# Xmega.net
KiCad netlist of a schematic drawn in EAGLE
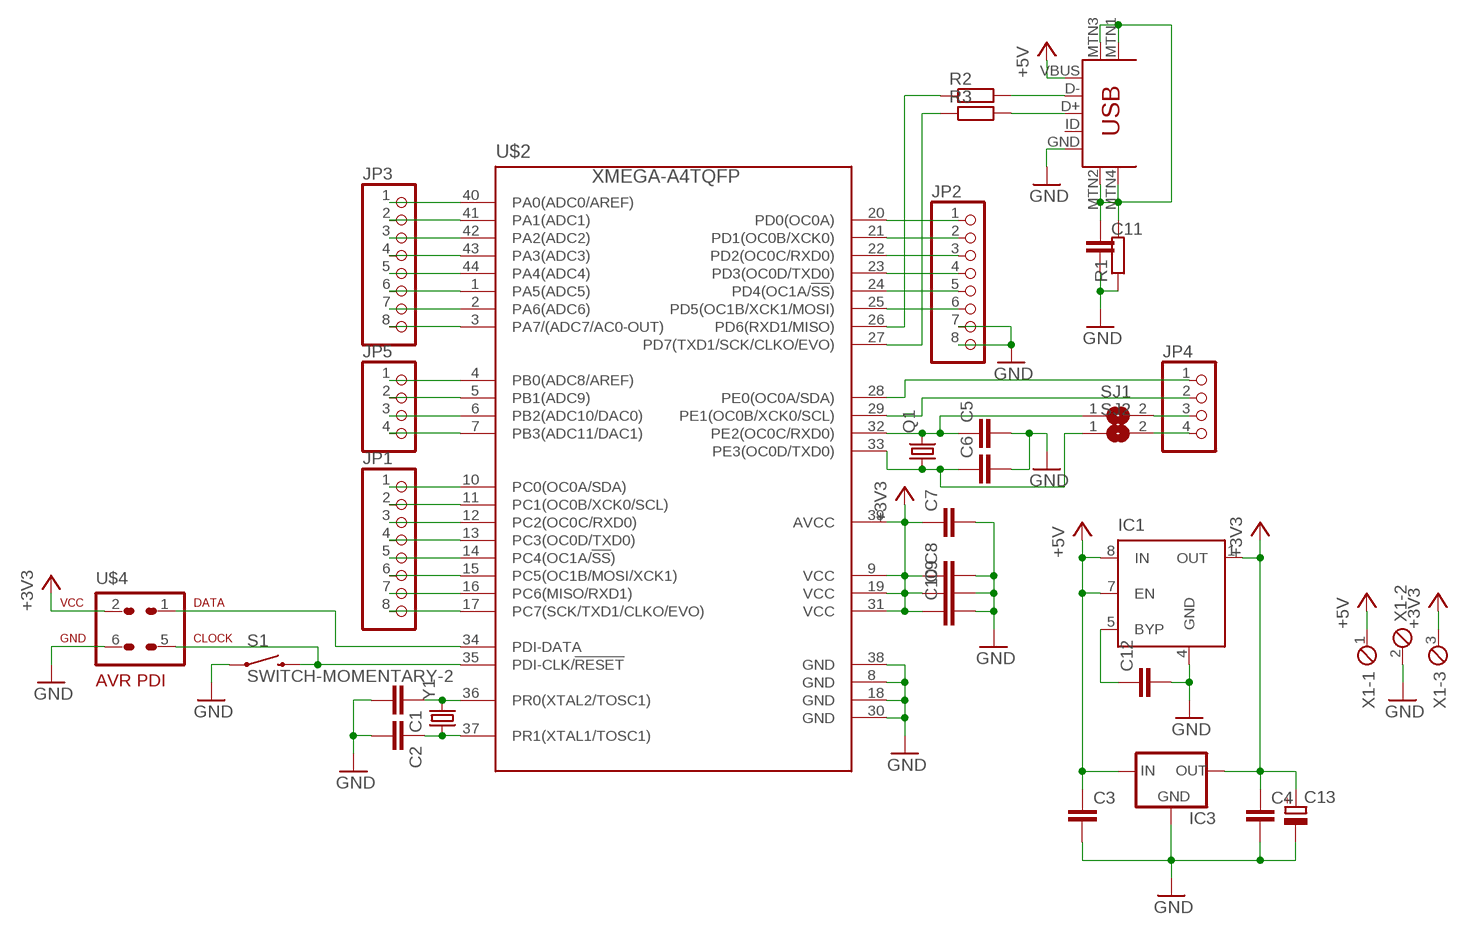
[diagram p0: schematic, sheet 1]

(export (version "E")
  (design (tool "Eeschema 10.0.6"))
  (components
    (comp (ref "C1")
      (value "C-EUC0603")
      (footprint "eagle-import:C0603")
      (libsource (lib "eagle-import") (part "C-EUC0603"))
    )
    (comp (ref "C2")
      (value "C-EUC0603")
      (footprint "eagle-import:C0603")
      (libsource (lib "eagle-import") (part "C-EUC0603"))
    )
    (comp (ref "C3")
      (value "C-EUC0805")
      (footprint "eagle-import:C0805")
      (libsource (lib "eagle-import") (part "C-EUC0805"))
    )
    (comp (ref "C4")
      (value "C-EUC0805")
      (footprint "eagle-import:C0805")
      (libsource (lib "eagle-import") (part "C-EUC0805"))
    )
    (comp (ref "C5")
      (value "C-EUC0603")
      (footprint "eagle-import:C0603")
      (libsource (lib "eagle-import") (part "C-EUC0603"))
    )
    (comp (ref "C6")
      (value "C-EUC0603")
      (footprint "eagle-import:C0603")
      (libsource (lib "eagle-import") (part "C-EUC0603"))
    )
    (comp (ref "C7")
      (value "C-EUC0603")
      (footprint "eagle-import:C0603")
      (libsource (lib "eagle-import") (part "C-EUC0603"))
    )
    (comp (ref "C8")
      (value "C-EUC0603")
      (footprint "eagle-import:C0603")
      (libsource (lib "eagle-import") (part "C-EUC0603"))
    )
    (comp (ref "C9")
      (value "C-EUC0603")
      (footprint "eagle-import:C0603")
      (libsource (lib "eagle-import") (part "C-EUC0603"))
    )
    (comp (ref "C10")
      (value "C-EUC0603")
      (footprint "eagle-import:C0603")
      (libsource (lib "eagle-import") (part "C-EUC0603"))
    )
    (comp (ref "C11")
      (value "C-EUC0603")
      (footprint "eagle-import:C0603")
      (libsource (lib "eagle-import") (part "C-EUC0603"))
    )
    (comp (ref "C12")
      (value "C-EUC0603")
      (footprint "eagle-import:C0603")
      (libsource (lib "eagle-import") (part "C-EUC0603"))
    )
    (comp (ref "C13")
      (value "CPOL-EUSMCB")
      (footprint "eagle-import:SMC_B")
      (libsource (lib "eagle-import") (part "CPOL-EUSMCB"))
    )
    (comp (ref "IC1")
      (value "TC1269")
      (footprint "eagle-import:MSOP08")
      (libsource (lib "eagle-import") (part "TC1269"))
    )
    (comp (ref "IC3")
      (value "VREG_3PIN_O-G-ITO92_MID")
      (footprint "eagle-import:TO92_MID")
      (libsource (lib "eagle-import") (part "VREG_3PIN_O-G-ITO92_MID"))
    )
    (comp (ref "JP1")
      (value "PINHD_FIXEDPAD_ROUND-1X8")
      (footprint "eagle-import:1X08_ROUND")
      (libsource (lib "eagle-import") (part "PINHD_FIXEDPAD_ROUND-1X8"))
    )
    (comp (ref "JP2")
      (value "PINHD_FIXEDPAD_ROUND-1X8")
      (footprint "eagle-import:1X08_ROUND")
      (libsource (lib "eagle-import") (part "PINHD_FIXEDPAD_ROUND-1X8"))
    )
    (comp (ref "JP3")
      (value "PINHD_FIXEDPAD_ROUND-1X8")
      (footprint "eagle-import:1X08_ROUND")
      (libsource (lib "eagle-import") (part "PINHD_FIXEDPAD_ROUND-1X8"))
    )
    (comp (ref "JP4")
      (value "PINHD_FIXEDPAD_ROUND-1X4")
      (footprint "eagle-import:1X04_ROUND")
      (libsource (lib "eagle-import") (part "PINHD_FIXEDPAD_ROUND-1X4"))
    )
    (comp (ref "JP5")
      (value "PINHD_FIXEDPAD_ROUND-1X4")
      (footprint "eagle-import:1X04_ROUND")
      (libsource (lib "eagle-import") (part "PINHD_FIXEDPAD_ROUND-1X4"))
    )
    (comp (ref "Q1")
      (value "CRYSTALTC26V")
      (footprint "eagle-import:TC26V")
      (libsource (lib "eagle-import") (part "CRYSTALTC26V"))
    )
    (comp (ref "R1")
      (value "R-EU_R0603")
      (footprint "eagle-import:R0603")
      (libsource (lib "eagle-import") (part "R-EU_R0603"))
    )
    (comp (ref "R2")
      (value "R-EU_R0603")
      (footprint "eagle-import:R0603")
      (libsource (lib "eagle-import") (part "R-EU_R0603"))
    )
    (comp (ref "R3")
      (value "R-EU_R0603")
      (footprint "eagle-import:R0603")
      (libsource (lib "eagle-import") (part "R-EU_R0603"))
    )
    (comp (ref "S1")
      (value "SWITCH-MOMENTARY-2")
      (footprint "eagle-import:TACTILE_SWITCH_TALL")
      (libsource (lib "eagle-import") (part "SWITCH-MOMENTARY-2"))
    )
    (comp (ref "SJ1")
      (value "SJ_SMALL")
      (footprint "eagle-import:SJ_2S-NO")
      (libsource (lib "eagle-import") (part "SJ_SMALL"))
    )
    (comp (ref "SJ2")
      (value "SJ_SMALL")
      (footprint "eagle-import:SJ_2S-NO")
      (libsource (lib "eagle-import") (part "SJ_SMALL"))
    )
    (comp (ref "U$1")
      (value "USB-MINIB-5PIN")
      (footprint "eagle-import:USB-MINIB")
      (libsource (lib "eagle-import") (part "USB-MINIB-5PIN"))
    )
    (comp (ref "U$2")
      (value "XMEGA-A4TQFP")
      (footprint "eagle-import:TQFP44")
      (libsource (lib "eagle-import") (part "XMEGA-A4TQFP"))
    )
    (comp (ref "U$4")
      (value "AVR-PDIVERT")
      (footprint "eagle-import:AVR-ISP-6")
      (libsource (lib "eagle-import") (part "AVR-PDIVERT"))
    )
    (comp (ref "X1")
      (value "MPT3")
      (footprint "eagle-import:3POL254")
      (libsource (lib "eagle-import") (part "MPT3"))
    )
    (comp (ref "Y1")
      (value "CRYSTAL5X3")
      (footprint "eagle-import:CRYSTAL-SMD-5X3")
      (libsource (lib "eagle-import") (part "CRYSTAL5X3"))
    )
  )
  (nets
    (net (code "1") (name "+3V3") (class "Default")
      (node (ref "C10") (pin "1") (pinfunction "1_1") (pintype "passive"))
      (node (ref "C13") (pin "+") (pinfunction "+_+") (pintype "passive"))
      (node (ref "C4") (pin "1") (pinfunction "1_1") (pintype "passive"))
      (node (ref "C7") (pin "1") (pinfunction "1_1") (pintype "passive"))
      (node (ref "C8") (pin "1") (pinfunction "1_1") (pintype "passive"))
      (node (ref "C9") (pin "1") (pinfunction "1_1") (pintype "passive"))
      (node (ref "IC1") (pin "1") (pinfunction "OUT_1") (pintype "output"))
      (node (ref "IC3") (pin "1") (pinfunction "OUT_1") (pintype "output"))
      (node (ref "U$2") (pin "19") (pinfunction "VCC_19") (pintype "power_in"))
      (node (ref "U$2") (pin "31") (pinfunction "VCC_31") (pintype "power_in"))
      (node (ref "U$2") (pin "39") (pinfunction "AVCC_39") (pintype "power_in"))
      (node (ref "U$2") (pin "9") (pinfunction "VCC_9") (pintype "power_in"))
      (node (ref "U$4") (pin "2") (pinfunction "2_2") (pintype "passive"))
      (node (ref "X1") (pin "3") (pinfunction "1_3") (pintype "passive"))
    )
    (net (code "2") (name "+5V") (class "Default")
      (node (ref "C3") (pin "1") (pinfunction "1_1") (pintype "passive"))
      (node (ref "IC1") (pin "7") (pinfunction "EN_7") (pintype "input"))
      (node (ref "IC1") (pin "8") (pinfunction "IN_8") (pintype "input"))
      (node (ref "IC3") (pin "3") (pinfunction "IN_3") (pintype "input"))
      (node (ref "U$1") (pin "VBUS") (pinfunction "VBUS_VBUS") (pintype "bidirectional"))
      (node (ref "X1") (pin "1") (pinfunction "1_1") (pintype "passive"))
    )
    (net (code "3") (name "GND") (class "Default")
      (node (ref "C1") (pin "2") (pinfunction "2_2") (pintype "passive"))
      (node (ref "C10") (pin "2") (pinfunction "2_2") (pintype "passive"))
      (node (ref "C11") (pin "2") (pinfunction "2_2") (pintype "passive"))
      (node (ref "C12") (pin "2") (pinfunction "2_2") (pintype "passive"))
      (node (ref "C13") (pin "-") (pinfunction "-_-") (pintype "passive"))
      (node (ref "C2") (pin "2") (pinfunction "2_2") (pintype "passive"))
      (node (ref "C3") (pin "2") (pinfunction "2_2") (pintype "passive"))
      (node (ref "C4") (pin "2") (pinfunction "2_2") (pintype "passive"))
      (node (ref "C5") (pin "2") (pinfunction "2_2") (pintype "passive"))
      (node (ref "C6") (pin "2") (pinfunction "2_2") (pintype "passive"))
      (node (ref "C7") (pin "2") (pinfunction "2_2") (pintype "passive"))
      (node (ref "C8") (pin "2") (pinfunction "2_2") (pintype "passive"))
      (node (ref "C9") (pin "2") (pinfunction "2_2") (pintype "passive"))
      (node (ref "IC1") (pin "4") (pinfunction "GND_4") (pintype "power_in"))
      (node (ref "IC3") (pin "2") (pinfunction "GND_2") (pintype "input"))
      (node (ref "JP2") (pin "7") (pinfunction "7_7") (pintype "passive"))
      (node (ref "JP2") (pin "8") (pinfunction "8_8") (pintype "passive"))
      (node (ref "R1") (pin "1") (pinfunction "1_1") (pintype "passive"))
      (node (ref "S1") (pin "A2") (pinfunction "1_A2") (pintype "passive"))
      (node (ref "U$1") (pin "GND") (pinfunction "GND_GND") (pintype "bidirectional"))
      (node (ref "U$2") (pin "18") (pinfunction "GND_18") (pintype "power_in"))
      (node (ref "U$2") (pin "30") (pinfunction "GND_30") (pintype "power_in"))
      (node (ref "U$2") (pin "38") (pinfunction "GND_38") (pintype "power_in"))
      (node (ref "U$2") (pin "8") (pinfunction "GND_8") (pintype "power_in"))
      (node (ref "U$4") (pin "6") (pinfunction "6_6") (pintype "passive"))
      (node (ref "X1") (pin "2") (pinfunction "1_2") (pintype "passive"))
    )
    (net (code "4") (name "Net-(IC1-BYP)") (class "Default")
      (node (ref "C12") (pin "1") (pinfunction "1_1") (pintype "passive"))
      (node (ref "IC1") (pin "5") (pinfunction "BYP_5") (pintype "passive"))
    )
    (net (code "5") (name "Net-(JP4-Pad3)") (class "Default")
      (node (ref "JP4") (pin "3") (pinfunction "3_3") (pintype "passive"))
      (node (ref "SJ1") (pin "2") (pinfunction "2_2") (pintype "passive"))
    )
    (net (code "6") (name "Net-(JP4-Pad4)") (class "Default")
      (node (ref "JP4") (pin "4") (pinfunction "4_4") (pintype "passive"))
      (node (ref "SJ2") (pin "2") (pinfunction "2_2") (pintype "passive"))
    )
    (net (code "7") (name "Net-(R2-Pad2)") (class "Default")
      (node (ref "R2") (pin "2") (pinfunction "2_2") (pintype "passive"))
      (node (ref "U$1") (pin "D-") (pinfunction "D-_D-") (pintype "bidirectional"))
    )
    (net (code "8") (name "Net-(R3-Pad2)") (class "Default")
      (node (ref "R3") (pin "2") (pinfunction "2_2") (pintype "passive"))
      (node (ref "U$1") (pin "D+") (pinfunction "D+_D+") (pintype "bidirectional"))
    )
    (net (code "9") (name "Net-(S1-2)") (class "Default")
      (node (ref "S1") (pin "B2") (pinfunction "2_B2") (pintype "passive"))
      (node (ref "U$2") (pin "35") (pinfunction "PDI-CLK/~{RESET}_35") (pintype "input"))
      (node (ref "U$4") (pin "5") (pinfunction "5_5") (pintype "passive"))
    )
    (net (code "10") (name "Net-(U$1-MTN1)") (class "Default")
      (node (ref "C11") (pin "1") (pinfunction "1_1") (pintype "passive"))
      (node (ref "R1") (pin "2") (pinfunction "2_2") (pintype "passive"))
      (node (ref "U$1") (pin "MTN1") (pinfunction "MTN2_MTN1") (pintype "bidirectional"))
      (node (ref "U$1") (pin "MTN2") (pinfunction "MTN3_MTN2") (pintype "bidirectional"))
      (node (ref "U$1") (pin "MTN3") (pinfunction "MTN1_MTN3") (pintype "bidirectional"))
      (node (ref "U$1") (pin "MTN4") (pinfunction "MTN4_MTN4") (pintype "bidirectional"))
    )
    (net (code "11") (name "Net-(U$2-PA0(ADC0{slash}AREF))") (class "Default")
      (node (ref "JP3") (pin "1") (pinfunction "1_1") (pintype "passive"))
      (node (ref "U$2") (pin "40") (pinfunction "PA0(ADC0/AREF)_40") (pintype "bidirectional"))
    )
    (net (code "12") (name "Net-(U$2-PA1(ADC1))") (class "Default")
      (node (ref "JP3") (pin "2") (pinfunction "2_2") (pintype "passive"))
      (node (ref "U$2") (pin "41") (pinfunction "PA1(ADC1)_41") (pintype "bidirectional"))
    )
    (net (code "13") (name "Net-(U$2-PA2(ADC2))") (class "Default")
      (node (ref "JP3") (pin "3") (pinfunction "3_3") (pintype "passive"))
      (node (ref "U$2") (pin "42") (pinfunction "PA2(ADC2)_42") (pintype "bidirectional"))
    )
    (net (code "14") (name "Net-(U$2-PA3(ADC3))") (class "Default")
      (node (ref "JP3") (pin "4") (pinfunction "4_4") (pintype "passive"))
      (node (ref "U$2") (pin "43") (pinfunction "PA3(ADC3)_43") (pintype "bidirectional"))
    )
    (net (code "15") (name "Net-(U$2-PA4(ADC4))") (class "Default")
      (node (ref "JP3") (pin "5") (pinfunction "5_5") (pintype "passive"))
      (node (ref "U$2") (pin "44") (pinfunction "PA4(ADC4)_44") (pintype "bidirectional"))
    )
    (net (code "16") (name "Net-(U$2-PA5(ADC5))") (class "Default")
      (node (ref "JP3") (pin "6") (pinfunction "6_6") (pintype "passive"))
      (node (ref "U$2") (pin "1") (pinfunction "PA5(ADC5)_1") (pintype "bidirectional"))
    )
    (net (code "17") (name "Net-(U$2-PA6(ADC6))") (class "Default")
      (node (ref "JP3") (pin "7") (pinfunction "7_7") (pintype "passive"))
      (node (ref "U$2") (pin "2") (pinfunction "PA6(ADC6)_2") (pintype "bidirectional"))
    )
    (net (code "18") (name "Net-(U$2-PA7{slash}(ADC7{slash}AC0-OUT))") (class "Default")
      (node (ref "JP3") (pin "8") (pinfunction "8_8") (pintype "passive"))
      (node (ref "U$2") (pin "3") (pinfunction "PA7/(ADC7/AC0-OUT)_3") (pintype "bidirectional"))
    )
    (net (code "19") (name "Net-(U$2-PB0(ADC8{slash}AREF))") (class "Default")
      (node (ref "JP5") (pin "1") (pinfunction "1_1") (pintype "passive"))
      (node (ref "U$2") (pin "4") (pinfunction "PB0(ADC8/AREF)_4") (pintype "bidirectional"))
    )
    (net (code "20") (name "Net-(U$2-PB1(ADC9))") (class "Default")
      (node (ref "JP5") (pin "2") (pinfunction "2_2") (pintype "passive"))
      (node (ref "U$2") (pin "5") (pinfunction "PB1(ADC9)_5") (pintype "bidirectional"))
    )
    (net (code "21") (name "Net-(U$2-PB2(ADC10{slash}DAC0))") (class "Default")
      (node (ref "JP5") (pin "3") (pinfunction "3_3") (pintype "passive"))
      (node (ref "U$2") (pin "6") (pinfunction "PB2(ADC10/DAC0)_6") (pintype "bidirectional"))
    )
    (net (code "22") (name "Net-(U$2-PB3(ADC11{slash}DAC1))") (class "Default")
      (node (ref "JP5") (pin "4") (pinfunction "4_4") (pintype "passive"))
      (node (ref "U$2") (pin "7") (pinfunction "PB3(ADC11/DAC1)_7") (pintype "bidirectional"))
    )
    (net (code "23") (name "Net-(U$2-PC0(OC0A{slash}SDA))") (class "Default")
      (node (ref "JP1") (pin "1") (pinfunction "1_1") (pintype "passive"))
      (node (ref "U$2") (pin "10") (pinfunction "PC0(OC0A/SDA)_10") (pintype "bidirectional"))
    )
    (net (code "24") (name "Net-(U$2-PC1(OC0B{slash}XCK0{slash}SCL))") (class "Default")
      (node (ref "JP1") (pin "2") (pinfunction "2_2") (pintype "passive"))
      (node (ref "U$2") (pin "11") (pinfunction "PC1(OC0B/XCK0/SCL)_11") (pintype "bidirectional"))
    )
    (net (code "25") (name "Net-(U$2-PC2(OC0C{slash}RXD0))") (class "Default")
      (node (ref "JP1") (pin "3") (pinfunction "3_3") (pintype "passive"))
      (node (ref "U$2") (pin "12") (pinfunction "PC2(OC0C/RXD0)_12") (pintype "bidirectional"))
    )
    (net (code "26") (name "Net-(U$2-PC3(OC0D{slash}TXD0))") (class "Default")
      (node (ref "JP1") (pin "4") (pinfunction "4_4") (pintype "passive"))
      (node (ref "U$2") (pin "13") (pinfunction "PC3(OC0D/TXD0)_13") (pintype "bidirectional"))
    )
    (net (code "27") (name "Net-(U$2-PC4(OC1A{slash}~{SS}))") (class "Default")
      (node (ref "JP1") (pin "5") (pinfunction "5_5") (pintype "passive"))
      (node (ref "U$2") (pin "14") (pinfunction "PC4(OC1A/~{SS})_14") (pintype "bidirectional"))
    )
    (net (code "28") (name "Net-(U$2-PC5(OC1B{slash}MOSI{slash}XCK1))") (class "Default")
      (node (ref "JP1") (pin "6") (pinfunction "6_6") (pintype "passive"))
      (node (ref "U$2") (pin "15") (pinfunction "PC5(OC1B/MOSI/XCK1)_15") (pintype "bidirectional"))
    )
    (net (code "29") (name "Net-(U$2-PC6(MISO{slash}RXD1))") (class "Default")
      (node (ref "JP1") (pin "7") (pinfunction "7_7") (pintype "passive"))
      (node (ref "U$2") (pin "16") (pinfunction "PC6(MISO/RXD1)_16") (pintype "bidirectional"))
    )
    (net (code "30") (name "Net-(U$2-PC7(SCK{slash}TXD1{slash}CLKO{slash}EVO))") (class "Default")
      (node (ref "JP1") (pin "8") (pinfunction "8_8") (pintype "passive"))
      (node (ref "U$2") (pin "17") (pinfunction "PC7(SCK/TXD1/CLKO/EVO)_17") (pintype "bidirectional"))
    )
    (net (code "31") (name "Net-(U$2-PD0(OC0A))") (class "Default")
      (node (ref "JP2") (pin "1") (pinfunction "1_1") (pintype "passive"))
      (node (ref "U$2") (pin "20") (pinfunction "PD0(OC0A)_20") (pintype "bidirectional"))
    )
    (net (code "32") (name "Net-(U$2-PD1(OC0B{slash}XCK0))") (class "Default")
      (node (ref "JP2") (pin "2") (pinfunction "2_2") (pintype "passive"))
      (node (ref "U$2") (pin "21") (pinfunction "PD1(OC0B/XCK0)_21") (pintype "bidirectional"))
    )
    (net (code "33") (name "Net-(U$2-PD2(OC0C{slash}RXD0))") (class "Default")
      (node (ref "JP2") (pin "3") (pinfunction "3_3") (pintype "passive"))
      (node (ref "U$2") (pin "22") (pinfunction "PD2(OC0C/RXD0)_22") (pintype "bidirectional"))
    )
    (net (code "34") (name "Net-(U$2-PD3(OC0D{slash}TXD0))") (class "Default")
      (node (ref "JP2") (pin "4") (pinfunction "4_4") (pintype "passive"))
      (node (ref "U$2") (pin "23") (pinfunction "PD3(OC0D/TXD0)_23") (pintype "bidirectional"))
    )
    (net (code "35") (name "Net-(U$2-PD4(OC1A{slash}~{SS}))") (class "Default")
      (node (ref "JP2") (pin "5") (pinfunction "5_5") (pintype "passive"))
      (node (ref "U$2") (pin "24") (pinfunction "PD4(OC1A/~{SS})_24") (pintype "bidirectional"))
    )
    (net (code "36") (name "Net-(U$2-PD5(OC1B{slash}XCK1{slash}MOSI))") (class "Default")
      (node (ref "JP2") (pin "6") (pinfunction "6_6") (pintype "passive"))
      (node (ref "U$2") (pin "25") (pinfunction "PD5(OC1B/XCK1/MOSI)_25") (pintype "bidirectional"))
    )
    (net (code "37") (name "Net-(U$2-PD6(RXD1{slash}MISO))") (class "Default")
      (node (ref "R2") (pin "1") (pinfunction "1_1") (pintype "passive"))
      (node (ref "U$2") (pin "26") (pinfunction "PD6(RXD1/MISO)_26") (pintype "bidirectional"))
    )
    (net (code "38") (name "Net-(U$2-PD7(TXD1{slash}SCK{slash}CLKO{slash}EVO))") (class "Default")
      (node (ref "R3") (pin "1") (pinfunction "1_1") (pintype "passive"))
      (node (ref "U$2") (pin "27") (pinfunction "PD7(TXD1/SCK/CLKO/EVO)_27") (pintype "bidirectional"))
    )
    (net (code "39") (name "Net-(U$2-PDI-DATA)") (class "Default")
      (node (ref "U$2") (pin "34") (pinfunction "PDI-DATA_34") (pintype "bidirectional"))
      (node (ref "U$4") (pin "1") (pinfunction "1_1") (pintype "passive"))
    )
    (net (code "40") (name "Net-(U$2-PE0(OC0A{slash}SDA))") (class "Default")
      (node (ref "JP4") (pin "1") (pinfunction "1_1") (pintype "passive"))
      (node (ref "U$2") (pin "28") (pinfunction "PE0(OC0A/SDA)_28") (pintype "bidirectional"))
    )
    (net (code "41") (name "Net-(U$2-PE1(OC0B{slash}XCK0{slash}SCL))") (class "Default")
      (node (ref "JP4") (pin "2") (pinfunction "2_2") (pintype "passive"))
      (node (ref "U$2") (pin "29") (pinfunction "PE1(OC0B/XCK0/SCL)_29") (pintype "bidirectional"))
    )
    (net (code "42") (name "Net-(U$2-PE2(OC0C{slash}RXD0))") (class "Default")
      (node (ref "C5") (pin "1") (pinfunction "1_1") (pintype "passive"))
      (node (ref "Q1") (pin "2") (pinfunction "2_2") (pintype "passive"))
      (node (ref "SJ1") (pin "1") (pinfunction "1_1") (pintype "passive"))
      (node (ref "U$2") (pin "32") (pinfunction "PE2(OC0C/RXD0)_32") (pintype "bidirectional"))
    )
    (net (code "43") (name "Net-(U$2-PE3(OC0D{slash}TXD0))") (class "Default")
      (node (ref "C6") (pin "1") (pinfunction "1_1") (pintype "passive"))
      (node (ref "Q1") (pin "1") (pinfunction "1_1") (pintype "passive"))
      (node (ref "SJ2") (pin "1") (pinfunction "1_1") (pintype "passive"))
      (node (ref "U$2") (pin "33") (pinfunction "PE3(OC0D/TXD0)_33") (pintype "bidirectional"))
    )
    (net (code "44") (name "Net-(U$2-PR0(XTAL2{slash}TOSC1))") (class "Default")
      (node (ref "C1") (pin "1") (pinfunction "1_1") (pintype "passive"))
      (node (ref "U$2") (pin "36") (pinfunction "PR0(XTAL2/TOSC1)_36") (pintype "bidirectional"))
      (node (ref "Y1") (pin "3") (pinfunction "2_3") (pintype "passive"))
    )
    (net (code "45") (name "Net-(U$2-PR1(XTAL1{slash}TOSC1))") (class "Default")
      (node (ref "C2") (pin "1") (pinfunction "1_1") (pintype "passive"))
      (node (ref "U$2") (pin "37") (pinfunction "PR1(XTAL1/TOSC1)_37") (pintype "bidirectional"))
      (node (ref "Y1") (pin "1") (pinfunction "1_1") (pintype "passive"))
    )
    (net (code "46") (name "unconnected-(U$1-PadID)") (class "Default")
      (node (ref "U$1") (pin "ID") (pinfunction "ID_ID") (pintype "bidirectional"))
    )
  )
)
